# RAMPS_1-3i.net
KiCad netlist of a schematic drawn in EAGLE
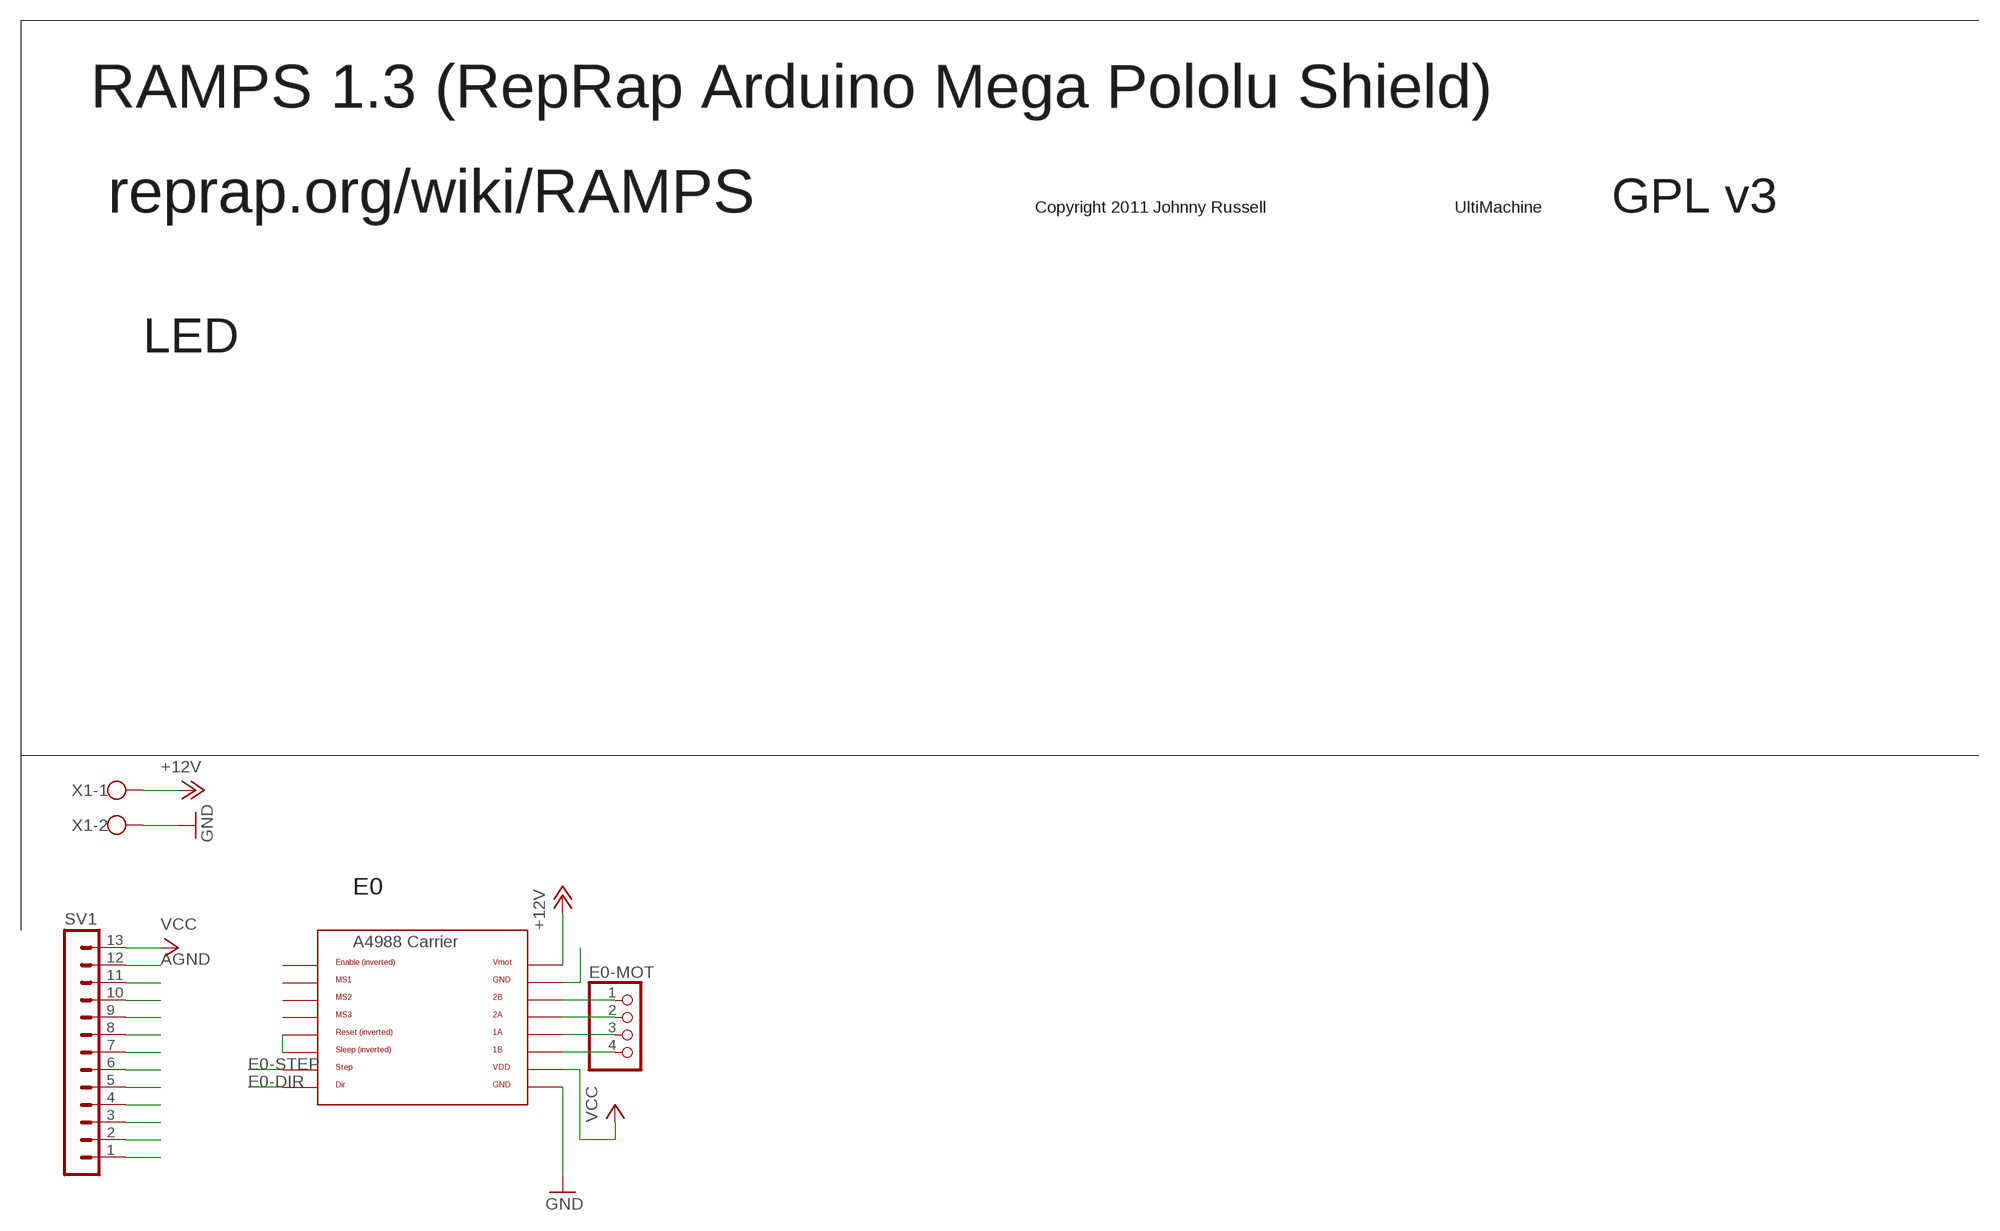
[diagram p0: schematic, sheet 1]

(export (version "E")
  (design (tool "Eeschema 10.0.6"))
  (components
    (comp (ref "E0-MOT")
      (value "PINHD-1X4")
      (footprint "eagle-import:1X04")
      (libsource (lib "eagle-import") (part "PINHD-1X4"))
    )
    (comp (ref "SV1")
      (value "MA13-1")
      (footprint "eagle-import:MA13-1")
      (libsource (lib "eagle-import") (part "MA13-1"))
    )
    (comp (ref "U$4")
      (value "A4988BREAKOUT")
      (footprint "eagle-import:A4988BREAKOUT")
      (libsource (lib "eagle-import") (part "A4988BREAKOUT"))
    )
    (comp (ref "X1")
      (value "W237-102")
      (footprint "eagle-import:W237-102")
      (fields (field (name "MPN") "237-102"))
      (libsource (lib "eagle-import") (part "W237-102"))
    )
  )
  (nets
    (net (code "1") (name "+12V") (class "Default")
      (node (ref "U$4") (pin "VMOT") (pinfunction "VMOT_VMOT") (pintype "power_in"))
      (node (ref "X1") (pin "1") (pinfunction "KL_1") (pintype "passive"))
    )
    (net (code "2") (name "/AGND") (class "Default")
      (node (ref "SV1") (pin "12") (pinfunction "12_12") (pintype "passive"))
      (node (ref "U$4") (pin "GND") (pinfunction "GND_GND") (pintype "power_in"))
    )
    (net (code "3") (name "/E0-DIR") (class "Default")
      (node (ref "SV1") (pin "1") (pinfunction "1_1") (pintype "passive"))
      (node (ref "U$4") (pin "DIR") (pinfunction "DIR_DIR") (pintype "input"))
    )
    (net (code "4") (name "/E0-STEP") (class "Default")
      (node (ref "SV1") (pin "2") (pinfunction "2_2") (pintype "passive"))
      (node (ref "U$4") (pin "STEP") (pinfunction "STEP_STEP") (pintype "input"))
    )
    (net (code "5") (name "GND") (class "Default")
      (node (ref "U$4") (pin "GND@0") (pinfunction "GND_GND@0") (pintype "power_in"))
      (node (ref "X1") (pin "2") (pinfunction "KL_2") (pintype "passive"))
    )
    (net (code "6") (name "Net-(E0-MOT-Pad1)") (class "Default")
      (node (ref "E0-MOT") (pin "1") (pinfunction "1_1") (pintype "passive"))
      (node (ref "U$4") (pin "2B") (pinfunction "2B_2B") (pintype "output"))
    )
    (net (code "7") (name "Net-(E0-MOT-Pad2)") (class "Default")
      (node (ref "E0-MOT") (pin "2") (pinfunction "2_2") (pintype "passive"))
      (node (ref "U$4") (pin "2A") (pinfunction "2A_2A") (pintype "output"))
    )
    (net (code "8") (name "Net-(E0-MOT-Pad3)") (class "Default")
      (node (ref "E0-MOT") (pin "3") (pinfunction "3_3") (pintype "passive"))
      (node (ref "U$4") (pin "1A") (pinfunction "1A_1A") (pintype "output"))
    )
    (net (code "9") (name "Net-(E0-MOT-Pad4)") (class "Default")
      (node (ref "E0-MOT") (pin "4") (pinfunction "4_4") (pintype "passive"))
      (node (ref "U$4") (pin "1B") (pinfunction "1B_1B") (pintype "output"))
    )
    (net (code "10") (name "Net-(U$4-SLEEP)") (class "Default")
      (node (ref "U$4") (pin "RST") (pinfunction "RST_RST") (pintype "input"))
      (node (ref "U$4") (pin "SLP") (pinfunction "SLEEP_SLP") (pintype "input"))
    )
    (net (code "11") (name "VCC") (class "Default")
      (node (ref "SV1") (pin "13") (pinfunction "13_13") (pintype "passive"))
      (node (ref "U$4") (pin "VDD") (pinfunction "VDD_VDD") (pintype "power_in"))
    )
    (net (code "12") (name "unconnected-(SV1-Pad3)") (class "Default")
      (node (ref "SV1") (pin "3") (pinfunction "3_3") (pintype "passive"))
    )
    (net (code "13") (name "unconnected-(SV1-Pad4)") (class "Default")
      (node (ref "SV1") (pin "4") (pinfunction "4_4") (pintype "passive"))
    )
    (net (code "14") (name "unconnected-(SV1-Pad5)") (class "Default")
      (node (ref "SV1") (pin "5") (pinfunction "5_5") (pintype "passive"))
    )
    (net (code "15") (name "unconnected-(SV1-Pad6)") (class "Default")
      (node (ref "SV1") (pin "6") (pinfunction "6_6") (pintype "passive"))
    )
    (net (code "16") (name "unconnected-(SV1-Pad7)") (class "Default")
      (node (ref "SV1") (pin "7") (pinfunction "7_7") (pintype "passive"))
    )
    (net (code "17") (name "unconnected-(SV1-Pad8)") (class "Default")
      (node (ref "SV1") (pin "8") (pinfunction "8_8") (pintype "passive"))
    )
    (net (code "18") (name "unconnected-(SV1-Pad9)") (class "Default")
      (node (ref "SV1") (pin "9") (pinfunction "9_9") (pintype "passive"))
    )
    (net (code "19") (name "unconnected-(SV1-Pad10)") (class "Default")
      (node (ref "SV1") (pin "10") (pinfunction "10_10") (pintype "passive"))
    )
    (net (code "20") (name "unconnected-(SV1-Pad11)") (class "Default")
      (node (ref "SV1") (pin "11") (pinfunction "11_11") (pintype "passive"))
    )
    (net (code "21") (name "unconnected-(U$4-PadEN)") (class "Default")
      (node (ref "U$4") (pin "EN") (pinfunction "EN_EN") (pintype "input"))
    )
    (net (code "22") (name "unconnected-(U$4-PadMS1)") (class "Default")
      (node (ref "U$4") (pin "MS1") (pinfunction "MS1_MS1") (pintype "input"))
    )
    (net (code "23") (name "unconnected-(U$4-PadMS2)") (class "Default")
      (node (ref "U$4") (pin "MS2") (pinfunction "MS2_MS2") (pintype "input"))
    )
    (net (code "24") (name "unconnected-(U$4-PadMS3)") (class "Default")
      (node (ref "U$4") (pin "MS3") (pinfunction "MS3_MS3") (pintype "input"))
    )
  )
)
